# Schematic_v13.net
KiCad netlist of a schematic drawn in EAGLE
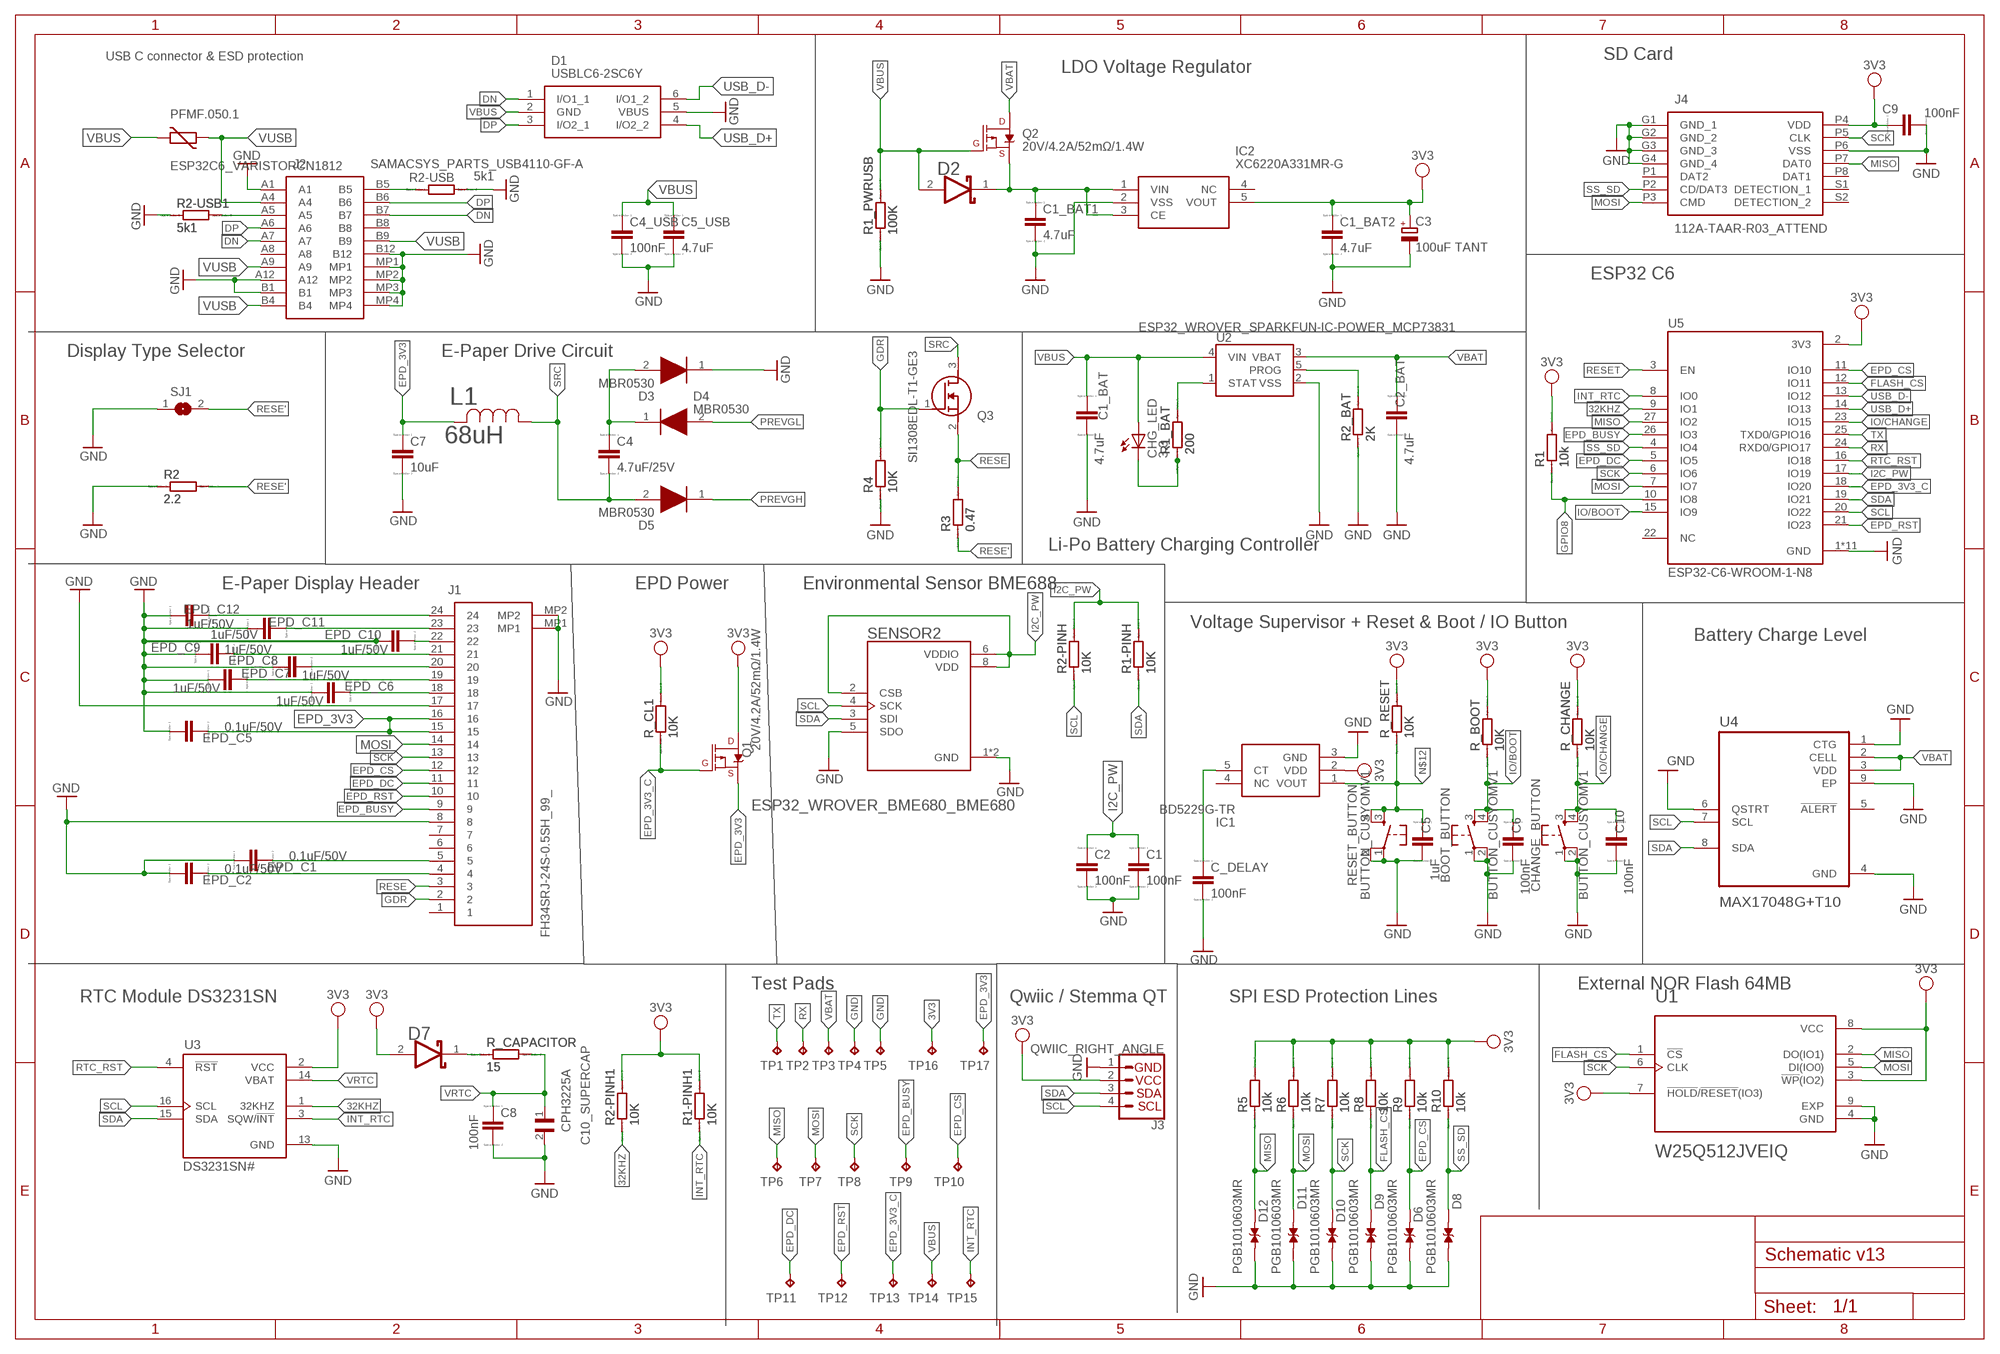
[diagram p0: schematic, sheet 1]

(export (version "E")
  (design (tool "Eeschema 10.0.6"))
  (components
    (comp (ref "BOOT_BUTTON")
      (value "BUTTON_CUSYOMV1")
      (footprint "eagle-import:MYBUTTON")
      (libsource (lib "eagle-import") (part "BUTTON_CUSYOMV1"))
    )
    (comp (ref "C1")
      (value "100nF")
      (footprint "eagle-import:ESP32_WROVER_EAGLE-LTSPICE_C0402")
      (libsource (lib "eagle-import") (part "ESP32_WROVER_EAGLE-LTSPICE_CC0402"))
    )
    (comp (ref "C1_BAT")
      (value "4.7uF")
      (footprint "eagle-import:ESP32_WROVER_EAGLE-LTSPICE_C0402")
      (libsource (lib "eagle-import") (part "ESP32_WROVER_EAGLE-LTSPICE_CC0402"))
    )
    (comp (ref "C1_BAT1")
      (value "4.7uF")
      (footprint "eagle-import:EAGLE-LTSPICE_C0402")
      (libsource (lib "eagle-import") (part "EAGLE-LTSPICE_CC0402"))
    )
    (comp (ref "C1_BAT2")
      (value "4.7uF")
      (footprint "eagle-import:EAGLE-LTSPICE_C0402")
      (libsource (lib "eagle-import") (part "EAGLE-LTSPICE_CC0402"))
    )
    (comp (ref "C2")
      (value "100nF")
      (footprint "eagle-import:ESP32_WROVER_EAGLE-LTSPICE_C0402")
      (libsource (lib "eagle-import") (part "ESP32_WROVER_EAGLE-LTSPICE_CC0402"))
    )
    (comp (ref "C2_BAT")
      (value "4.7uF")
      (footprint "eagle-import:ESP32_WROVER_EAGLE-LTSPICE_C0402")
      (libsource (lib "eagle-import") (part "ESP32_WROVER_EAGLE-LTSPICE_CC0402"))
    )
    (comp (ref "C3")
      (value "100uF TANT")
      (footprint "eagle-import:RCL_CT3528")
      (libsource (lib "eagle-import") (part "RCL_CPOL-EUCT3528"))
    )
    (comp (ref "C4")
      (value "4.7uF/25V")
      (footprint "eagle-import:ESP32_WROVER_EAGLE-LTSPICE_C0402")
      (libsource (lib "eagle-import") (part "ESP32_WROVER_EAGLE-LTSPICE_CC0402"))
    )
    (comp (ref "C4_USB")
      (value "100nF")
      (footprint "eagle-import:ESP32_WROVER_EAGLE-LTSPICE_C0402")
      (libsource (lib "eagle-import") (part "ESP32_WROVER_EAGLE-LTSPICE_CC0402"))
    )
    (comp (ref "C5")
      (value "1uF")
      (footprint "eagle-import:ESP32_WROVER_EAGLE-LTSPICE_C0402")
      (libsource (lib "eagle-import") (part "ESP32_WROVER_EAGLE-LTSPICE_CC0402"))
    )
    (comp (ref "C5_USB")
      (value "4.7uF")
      (footprint "eagle-import:ESP32_WROVER_EAGLE-LTSPICE_C0402")
      (libsource (lib "eagle-import") (part "ESP32_WROVER_EAGLE-LTSPICE_CC0402"))
    )
    (comp (ref "C6")
      (value "100nF")
      (footprint "eagle-import:ESP32_WROVER_EAGLE-LTSPICE_C0402")
      (libsource (lib "eagle-import") (part "ESP32_WROVER_EAGLE-LTSPICE_CC0402"))
    )
    (comp (ref "C7")
      (value "10uF")
      (footprint "eagle-import:ESP32_WROVER_EAGLE-LTSPICE_C0402")
      (libsource (lib "eagle-import") (part "ESP32_WROVER_EAGLE-LTSPICE_CC0402"))
    )
    (comp (ref "C8")
      (value "100nF")
      (footprint "eagle-import:ESP32_WROVER_EAGLE-LTSPICE_C0402")
      (libsource (lib "eagle-import") (part "ESP32_WROVER_EAGLE-LTSPICE_CC0402"))
    )
    (comp (ref "C9")
      (value "100nF")
      (footprint "eagle-import:ESP32_WROVER_EAGLE-LTSPICE_C0402")
      (libsource (lib "eagle-import") (part "ESP32_WROVER_EAGLE-LTSPICE_CC0402"))
    )
    (comp (ref "C10")
      (value "100nF")
      (footprint "eagle-import:ESP32_WROVER_EAGLE-LTSPICE_C0402")
      (libsource (lib "eagle-import") (part "ESP32_WROVER_EAGLE-LTSPICE_CC0402"))
    )
    (comp (ref "C10_SUPERCAP")
      (value "CPH3225A")
      (footprint "eagle-import:CAPCP3225X100N")
      (fields (field (name "MF") "Seiko Instruments"))
      (libsource (lib "eagle-import") (part "CPH3225A"))
    )
    (comp (ref "CHANGE_BUTTON")
      (value "BUTTON_CUSYOMV1")
      (footprint "eagle-import:MYBUTTON")
      (libsource (lib "eagle-import") (part "BUTTON_CUSYOMV1"))
    )
    (comp (ref "CHG_LED")
      (value "3.3")
      (footprint "eagle-import:ADAFRUIT_CHIP-LED0603")
      (libsource (lib "eagle-import") (part "ADAFRUIT_LEDCHIP-LED0603"))
    )
    (comp (ref "C_DELAY")
      (value "100nF")
      (footprint "eagle-import:ESP32_WROVER_EAGLE-LTSPICE_C0402")
      (libsource (lib "eagle-import") (part "ESP32_WROVER_EAGLE-LTSPICE_CC0402"))
    )
    (comp (ref "D1")
      (value "USBLC6-2SC6Y")
      (footprint "eagle-import:SOT95P280X145-6N")
      (fields (field (name "MF") "STMicroelectronics"))
      (libsource (lib "eagle-import") (part "USBLC6-2SC6Y"))
    )
    (comp (ref "D2")
      (value "ESP32_WROVER_AVX---SD0805S020S1R0_AVX_SD0805S020S1R0_0_0AVX_SD0805S020S1R0_0_0")
      (footprint "eagle-import:ESP32_WROVER_AVX---SD0805S020S1R0_AVX_SD0805S020S1R0_0")
      (fields
        (field (name "DIGIKEY_PART_NUMBER") "478-7800-1-ND")
        (field (name "MF") "AVX")
        (field (name "MOUSER_PART_NUMBER") "581-SD0805S020S1R0")
      )
      (libsource (lib "eagle-import") (part "ESP32_WROVER_AVX---SD0805S020S1R0_AVX_SD0805S020S1R0_0_0AVX_SD0805S020S1R0_0_0"))
    )
    (comp (ref "D3")
      (value "MBR0530")
      (footprint "eagle-import:SOD3716X135N")
      (fields (field (name "MF") "ON Semiconductor"))
      (libsource (lib "eagle-import") (part "MBR0530"))
    )
    (comp (ref "D4")
      (value "MBR0530")
      (footprint "eagle-import:SOD3716X135N")
      (fields (field (name "MF") "ON Semiconductor"))
      (libsource (lib "eagle-import") (part "MBR0530"))
    )
    (comp (ref "D5")
      (value "MBR0530")
      (footprint "eagle-import:SOD3716X135N")
      (fields (field (name "MF") "ON Semiconductor"))
      (libsource (lib "eagle-import") (part "MBR0530"))
    )
    (comp (ref "D6")
      (value "PGB1010603MR")
      (footprint "eagle-import:DIOC1608X36N")
      (fields (field (name "MF") "Littelfuse Inc."))
      (libsource (lib "eagle-import") (part "PGB1010603MR"))
    )
    (comp (ref "D7")
      (value "ESP32_WROVER_AVX---SD0805S020S1R0_AVX_SD0805S020S1R0_0_0AVX_SD0805S020S1R0_0_0")
      (footprint "eagle-import:ESP32_WROVER_AVX---SD0805S020S1R0_AVX_SD0805S020S1R0_0")
      (fields
        (field (name "DIGIKEY_PART_NUMBER") "478-7800-1-ND")
        (field (name "MF") "AVX")
        (field (name "MOUSER_PART_NUMBER") "581-SD0805S020S1R0")
      )
      (libsource (lib "eagle-import") (part "ESP32_WROVER_AVX---SD0805S020S1R0_AVX_SD0805S020S1R0_0_0AVX_SD0805S020S1R0_0_0"))
    )
    (comp (ref "D8")
      (value "PGB1010603MR")
      (footprint "eagle-import:DIOC1608X36N")
      (fields (field (name "MF") "Littelfuse Inc."))
      (libsource (lib "eagle-import") (part "PGB1010603MR"))
    )
    (comp (ref "D9")
      (value "PGB1010603MR")
      (footprint "eagle-import:DIOC1608X36N")
      (fields (field (name "MF") "Littelfuse Inc."))
      (libsource (lib "eagle-import") (part "PGB1010603MR"))
    )
    (comp (ref "D10")
      (value "PGB1010603MR")
      (footprint "eagle-import:DIOC1608X36N")
      (fields (field (name "MF") "Littelfuse Inc."))
      (libsource (lib "eagle-import") (part "PGB1010603MR"))
    )
    (comp (ref "D11")
      (value "PGB1010603MR")
      (footprint "eagle-import:DIOC1608X36N")
      (fields (field (name "MF") "Littelfuse Inc."))
      (libsource (lib "eagle-import") (part "PGB1010603MR"))
    )
    (comp (ref "D12")
      (value "PGB1010603MR")
      (footprint "eagle-import:DIOC1608X36N")
      (fields (field (name "MF") "Littelfuse Inc."))
      (libsource (lib "eagle-import") (part "PGB1010603MR"))
    )
    (comp (ref "EPD_C1")
      (value "0.1uF/50V")
      (footprint "eagle-import:ESP32_WROVER_EAGLE-LTSPICE_C0402")
      (libsource (lib "eagle-import") (part "ESP32_WROVER_EAGLE-LTSPICE_CC0402"))
    )
    (comp (ref "EPD_C2")
      (value "0.1uF/50V")
      (footprint "eagle-import:ESP32_WROVER_EAGLE-LTSPICE_C0402")
      (libsource (lib "eagle-import") (part "ESP32_WROVER_EAGLE-LTSPICE_CC0402"))
    )
    (comp (ref "EPD_C5")
      (value "0.1uF/50V")
      (footprint "eagle-import:ESP32_WROVER_EAGLE-LTSPICE_C0402")
      (libsource (lib "eagle-import") (part "ESP32_WROVER_EAGLE-LTSPICE_CC0402"))
    )
    (comp (ref "EPD_C6")
      (value "1uF/50V")
      (footprint "eagle-import:ESP32_WROVER_EAGLE-LTSPICE_C0402")
      (libsource (lib "eagle-import") (part "ESP32_WROVER_EAGLE-LTSPICE_CC0402"))
    )
    (comp (ref "EPD_C7")
      (value "1uF/50V")
      (footprint "eagle-import:ESP32_WROVER_EAGLE-LTSPICE_C0402")
      (libsource (lib "eagle-import") (part "ESP32_WROVER_EAGLE-LTSPICE_CC0402"))
    )
    (comp (ref "EPD_C8")
      (value "1uF/50V")
      (footprint "eagle-import:ESP32_WROVER_EAGLE-LTSPICE_C0402")
      (libsource (lib "eagle-import") (part "ESP32_WROVER_EAGLE-LTSPICE_CC0402"))
    )
    (comp (ref "EPD_C9")
      (value "1uF/50V")
      (footprint "eagle-import:ESP32_WROVER_EAGLE-LTSPICE_C0402")
      (libsource (lib "eagle-import") (part "ESP32_WROVER_EAGLE-LTSPICE_CC0402"))
    )
    (comp (ref "EPD_C10")
      (value "1uF/50V")
      (footprint "eagle-import:ESP32_WROVER_EAGLE-LTSPICE_C0402")
      (libsource (lib "eagle-import") (part "ESP32_WROVER_EAGLE-LTSPICE_CC0402"))
    )
    (comp (ref "EPD_C11")
      (value "1uF/50V")
      (footprint "eagle-import:ESP32_WROVER_EAGLE-LTSPICE_C0402")
      (libsource (lib "eagle-import") (part "ESP32_WROVER_EAGLE-LTSPICE_CC0402"))
    )
    (comp (ref "EPD_C12")
      (value "1uF/50V")
      (footprint "eagle-import:ESP32_WROVER_EAGLE-LTSPICE_C0402")
      (libsource (lib "eagle-import") (part "ESP32_WROVER_EAGLE-LTSPICE_CC0402"))
    )
    (comp (ref "IC1")
      (value "BD5229G-TR")
      (footprint "eagle-import:SOT95P280X125-5N")
      (fields (field (name "MOUSER_PART_NUMBER") "755-BD5229G-TR"))
      (libsource (lib "eagle-import") (part "BD5229G-TR"))
    )
    (comp (ref "IC2")
      (value "XC6220A331MR-G")
      (footprint "eagle-import:SOT95P280X120-5N")
      (fields (field (name "MOUSER_PART_NUMBER") "865-XC6220A331MR-G"))
      (libsource (lib "eagle-import") (part "XC6220A331MR-G"))
    )
    (comp (ref "J1")
      (value "FH34SRJ-24S-0.5SH_99_")
      (footprint "eagle-import:FH34SRJ24S05SH99")
      (fields
        (field (name "MANUFACTURER_PART_NUMBER") "FH34SRJ-24S-0.5SH(99)")
        (field (name "MOUSER_PART_NUMBER") "798-FH34SRJ24S05SH99")
      )
      (libsource (lib "eagle-import") (part "FH34SRJ-24S-0.5SH_99_"))
    )
    (comp (ref "J2")
      (value "SAMACSYS_PARTS_USB4110-GF-A")
      (footprint "eagle-import:SAMACSYS_PARTS_USB4110GFA")
      (fields
        (field (name "MANUFACTURER_PART_NUMBER") "USB4110-GF-A")
        (field (name "MOUSER_PART_NUMBER") "640-USB4110-GF-A")
      )
      (libsource (lib "eagle-import") (part "SAMACSYS_PARTS_USB4110-GF-A"))
    )
    (comp (ref "J3")
      (value "QWIIC_RIGHT_ANGLE")
      (footprint "eagle-import:JST04_1MM_RA")
      (libsource (lib "eagle-import") (part "QWIIC_CONNECTORJS-1MM"))
    )
    (comp (ref "J4")
      (value "112A-TAAR-R03_ATTEND")
      (footprint "eagle-import:112ATAARR03ATTEND")
      (fields (field (name "MANUFACTURER_PART_NUMBER") "112A-TAAR-R03 ATTEND"))
      (libsource (lib "eagle-import") (part "112A-TAAR-R03_ATTEND"))
    )
    (comp (ref "L1")
      (value "68uH")
      (footprint "eagle-import:IND_4828-WE-TPC_WRE")
      (fields
        (field (name "MANUFACTURER_PART_NUMBER") "744043680")
        (field (name "COPYRIGHT") "Copyright (C) 2024 Ultra Librarian. All rights reserved.")
      )
      (libsource (lib "eagle-import") (part "744043680IND_4828-WE-TPC_WRE"))
    )
    (comp (ref "PFMF.050.1")
      (value "ESP32C6_VARISTORCN1812")
      (footprint "eagle-import:ESP32C6_VARISTOR_CT_CN1812")
      (libsource (lib "eagle-import") (part "ESP32C6_VARISTORCN1812"))
    )
    (comp (ref "Q1")
      (value "20V/4.2A/52mΩ/1.4W")
      (footprint "eagle-import:ESP32_WROVER_SPARKFUN-DISCRETESEMI_SOT23-3")
      (libsource (lib "eagle-import") (part "ESP32_WROVER_SPARKFUN-DISCRETESEMI_MOSFET_PCH-DMG2305UX-7"))
    )
    (comp (ref "Q2")
      (value "20V/4.2A/52mΩ/1.4W")
      (footprint "eagle-import:ESP32_WROVER_SPARKFUN-DISCRETESEMI_SOT23-3")
      (libsource (lib "eagle-import") (part "ESP32_WROVER_SPARKFUN-DISCRETESEMI_MOSFET_PCH-DMG2305UX-7"))
    )
    (comp (ref "Q3")
      (value "SI1308EDL-T1-GE3")
      (footprint "eagle-import:SOT65P210X110-3N")
      (fields (field (name "MF") "Vishay Siliconix"))
      (libsource (lib "eagle-import") (part "SI1308EDL-T1-GE3"))
    )
    (comp (ref "R1")
      (value "10k")
      (footprint "eagle-import:ESP32_WROVER_EAGLE-LTSPICE_R0402")
      (libsource (lib "eagle-import") (part "ESP32_WROVER_EAGLE-LTSPICE_RR0402"))
    )
    (comp (ref "R1-PINH")
      (value "10K")
      (footprint "eagle-import:ESP32_WROVER_EAGLE-LTSPICE_R0402")
      (libsource (lib "eagle-import") (part "ESP32_WROVER_EAGLE-LTSPICE_RR0402"))
    )
    (comp (ref "R1-PINH1")
      (value "10K")
      (footprint "eagle-import:ESP32_WROVER_EAGLE-LTSPICE_R0402")
      (libsource (lib "eagle-import") (part "ESP32_WROVER_EAGLE-LTSPICE_RR0402"))
    )
    (comp (ref "R1_BAT")
      (value "200")
      (footprint "eagle-import:ESP32_WROVER_EAGLE-LTSPICE_R0402")
      (libsource (lib "eagle-import") (part "ESP32_WROVER_EAGLE-LTSPICE_RR0402"))
    )
    (comp (ref "R1_PWRUSB")
      (value "100K")
      (footprint "eagle-import:ESP32_WROVER_EAGLE-LTSPICE_R0402")
      (libsource (lib "eagle-import") (part "ESP32_WROVER_EAGLE-LTSPICE_RR0402"))
    )
    (comp (ref "R2")
      (value "2.2")
      (footprint "eagle-import:ESP32_WROVER_EAGLE-LTSPICE_R0402")
      (libsource (lib "eagle-import") (part "ESP32_WROVER_EAGLE-LTSPICE_RR0402"))
    )
    (comp (ref "R2-PINH")
      (value "10K")
      (footprint "eagle-import:ESP32_WROVER_EAGLE-LTSPICE_R0402")
      (libsource (lib "eagle-import") (part "ESP32_WROVER_EAGLE-LTSPICE_RR0402"))
    )
    (comp (ref "R2-PINH1")
      (value "10K")
      (footprint "eagle-import:ESP32_WROVER_EAGLE-LTSPICE_R0402")
      (libsource (lib "eagle-import") (part "ESP32_WROVER_EAGLE-LTSPICE_RR0402"))
    )
    (comp (ref "R2-USB")
      (value "5k1")
      (footprint "eagle-import:ESP32_WROVER_EAGLE-LTSPICE_R0402")
      (libsource (lib "eagle-import") (part "ESP32_WROVER_EAGLE-LTSPICE_RR0402"))
    )
    (comp (ref "R2-USB1")
      (value "5k1")
      (footprint "eagle-import:ESP32_WROVER_EAGLE-LTSPICE_R0402")
      (libsource (lib "eagle-import") (part "ESP32_WROVER_EAGLE-LTSPICE_RR0402"))
    )
    (comp (ref "R2_BAT")
      (value "2K")
      (footprint "eagle-import:ESP32_WROVER_EAGLE-LTSPICE_R0402")
      (libsource (lib "eagle-import") (part "ESP32_WROVER_EAGLE-LTSPICE_RR0402"))
    )
    (comp (ref "R3")
      (value "0.47")
      (footprint "eagle-import:ESP32_WROVER_EAGLE-LTSPICE_R0402")
      (libsource (lib "eagle-import") (part "ESP32_WROVER_EAGLE-LTSPICE_RR0402"))
    )
    (comp (ref "R4")
      (value "10K")
      (footprint "eagle-import:ESP32_WROVER_EAGLE-LTSPICE_R0402")
      (libsource (lib "eagle-import") (part "ESP32_WROVER_EAGLE-LTSPICE_RR0402"))
    )
    (comp (ref "R5")
      (value "10k")
      (footprint "eagle-import:ESP32_WROVER_EAGLE-LTSPICE_R0402")
      (libsource (lib "eagle-import") (part "ESP32_WROVER_EAGLE-LTSPICE_RR0402"))
    )
    (comp (ref "R6")
      (value "10k")
      (footprint "eagle-import:ESP32_WROVER_EAGLE-LTSPICE_R0402")
      (libsource (lib "eagle-import") (part "ESP32_WROVER_EAGLE-LTSPICE_RR0402"))
    )
    (comp (ref "R7")
      (value "10k")
      (footprint "eagle-import:ESP32_WROVER_EAGLE-LTSPICE_R0402")
      (libsource (lib "eagle-import") (part "ESP32_WROVER_EAGLE-LTSPICE_RR0402"))
    )
    (comp (ref "R8")
      (value "10k")
      (footprint "eagle-import:ESP32_WROVER_EAGLE-LTSPICE_R0402")
      (libsource (lib "eagle-import") (part "ESP32_WROVER_EAGLE-LTSPICE_RR0402"))
    )
    (comp (ref "R9")
      (value "10k")
      (footprint "eagle-import:ESP32_WROVER_EAGLE-LTSPICE_R0402")
      (libsource (lib "eagle-import") (part "ESP32_WROVER_EAGLE-LTSPICE_RR0402"))
    )
    (comp (ref "R10")
      (value "10k")
      (footprint "eagle-import:ESP32_WROVER_EAGLE-LTSPICE_R0402")
      (libsource (lib "eagle-import") (part "ESP32_WROVER_EAGLE-LTSPICE_RR0402"))
    )
    (comp (ref "RESET_BUTTON")
      (value "BUTTON_CUSYOMV1")
      (footprint "eagle-import:MYBUTTON")
      (libsource (lib "eagle-import") (part "BUTTON_CUSYOMV1"))
    )
    (comp (ref "R_BOOT")
      (value "10K")
      (footprint "eagle-import:ESP32_WROVER_EAGLE-LTSPICE_R0402")
      (libsource (lib "eagle-import") (part "ESP32_WROVER_EAGLE-LTSPICE_RR0402"))
    )
    (comp (ref "R_CAPACITOR")
      (value "15")
      (footprint "eagle-import:ESP32_WROVER_EAGLE-LTSPICE_R0402")
      (libsource (lib "eagle-import") (part "ESP32_WROVER_EAGLE-LTSPICE_RR0402"))
    )
    (comp (ref "R_CHANGE")
      (value "10K")
      (footprint "eagle-import:ESP32_WROVER_EAGLE-LTSPICE_R0402")
      (libsource (lib "eagle-import") (part "ESP32_WROVER_EAGLE-LTSPICE_RR0402"))
    )
    (comp (ref "R_CL1")
      (value "10K")
      (footprint "eagle-import:ESP32_WROVER_EAGLE-LTSPICE_R0402")
      (libsource (lib "eagle-import") (part "ESP32_WROVER_EAGLE-LTSPICE_RR0402"))
    )
    (comp (ref "R_RESET")
      (value "10K")
      (footprint "eagle-import:ESP32_WROVER_EAGLE-LTSPICE_R0402")
      (libsource (lib "eagle-import") (part "ESP32_WROVER_EAGLE-LTSPICE_RR0402"))
    )
    (comp (ref "SENSOR2")
      (value "ESP32_WROVER_BME680_BME680")
      (footprint "eagle-import:ESP32_WROVER_BME680_PSON80P300X300X100-8N")
      (fields (field (name "MF") "Bosch Sensortec") (field (name "MP") "BME680"))
      (libsource (lib "eagle-import") (part "ESP32_WROVER_BME680_BME680"))
    )
    (comp (ref "SJ1") (value "SJ") (footprint "eagle-import:SJ") (libsource (lib "eagle-import") (part "SJ")))
    (comp (ref "TP1")
      (value "TPTP20R")
      (footprint "eagle-import:TP20R")
      (libsource (lib "eagle-import") (part "TPTP20R"))
    )
    (comp (ref "TP2")
      (value "TPTP20R")
      (footprint "eagle-import:TP20R")
      (libsource (lib "eagle-import") (part "TPTP20R"))
    )
    (comp (ref "TP3")
      (value "TPTP20R")
      (footprint "eagle-import:TP20R")
      (libsource (lib "eagle-import") (part "TPTP20R"))
    )
    (comp (ref "TP4")
      (value "TPTP20R")
      (footprint "eagle-import:TP20R")
      (libsource (lib "eagle-import") (part "TPTP20R"))
    )
    (comp (ref "TP5")
      (value "TPTP20R")
      (footprint "eagle-import:TP20R")
      (libsource (lib "eagle-import") (part "TPTP20R"))
    )
    (comp (ref "TP6")
      (value "TPTP20R")
      (footprint "eagle-import:TP20R")
      (libsource (lib "eagle-import") (part "TPTP20R"))
    )
    (comp (ref "TP7")
      (value "TPTP20R")
      (footprint "eagle-import:TP20R")
      (libsource (lib "eagle-import") (part "TPTP20R"))
    )
    (comp (ref "TP8")
      (value "TPTP20R")
      (footprint "eagle-import:TP20R")
      (libsource (lib "eagle-import") (part "TPTP20R"))
    )
    (comp (ref "TP9")
      (value "TPTP20R")
      (footprint "eagle-import:TP20R")
      (libsource (lib "eagle-import") (part "TPTP20R"))
    )
    (comp (ref "TP10")
      (value "TPTP20R")
      (footprint "eagle-import:TP20R")
      (libsource (lib "eagle-import") (part "TPTP20R"))
    )
    (comp (ref "TP11")
      (value "TPTP20R")
      (footprint "eagle-import:TP20R")
      (libsource (lib "eagle-import") (part "TPTP20R"))
    )
    (comp (ref "TP12")
      (value "TPTP20R")
      (footprint "eagle-import:TP20R")
      (libsource (lib "eagle-import") (part "TPTP20R"))
    )
    (comp (ref "TP13")
      (value "TPTP20R")
      (footprint "eagle-import:TP20R")
      (libsource (lib "eagle-import") (part "TPTP20R"))
    )
    (comp (ref "TP14")
      (value "TPTP20R")
      (footprint "eagle-import:TP20R")
      (libsource (lib "eagle-import") (part "TPTP20R"))
    )
    (comp (ref "TP15")
      (value "TPTP20R")
      (footprint "eagle-import:TP20R")
      (libsource (lib "eagle-import") (part "TPTP20R"))
    )
    (comp (ref "TP16")
      (value "TPTP20R")
      (footprint "eagle-import:TP20R")
      (libsource (lib "eagle-import") (part "TPTP20R"))
    )
    (comp (ref "TP17")
      (value "TPTP20R")
      (footprint "eagle-import:TP20R")
      (libsource (lib "eagle-import") (part "TPTP20R"))
    )
    (comp (ref "U1")
      (value "W25Q512JVEIQ")
      (footprint "eagle-import:SON127P600X800X80-9N")
      (fields (field (name "MF") "Winbond Electronics"))
      (libsource (lib "eagle-import") (part "W25Q512JVEIQ"))
    )
    (comp (ref "U2")
      (value "ESP32_WROVER_SPARKFUN-IC-POWER_MCP73831")
      (footprint "eagle-import:ESP32_WROVER_SPARKFUN-IC-POWER_SOT23-5")
      (libsource (lib "eagle-import") (part "ESP32_WROVER_SPARKFUN-IC-POWER_MCP73831"))
    )
    (comp (ref "U3")
      (value "DS3231SN#")
      (footprint "eagle-import:SOIC127P1032X265-16N")
      (fields (field (name "MF") "Analog Devices"))
      (libsource (lib "eagle-import") (part "DS3231SN#"))
    )
    (comp (ref "U4")
      (value "MAX17048G+T10")
      (footprint "eagle-import:SON50P200X200X80-9N")
      (fields (field (name "MF") "Analog Devices"))
      (libsource (lib "eagle-import") (part "MAX17048G+T10"))
    )
    (comp (ref "U5")
      (value "ESP32-C6-WROOM-1-N8")
      (footprint "eagle-import:XCVR_ESP32-C6-WROOM-1-N8")
      (fields (field (name "MF") "Espressif Systems"))
      (libsource (lib "eagle-import") (part "ESP32-C6-WROOM-1-N8"))
    )
  )
  (nets
    (net (code "1") (name "3V3") (class "Default")
      (node (ref "C1_BAT2") (pin "1") (pinfunction "1_1") (pintype "passive"))
      (node (ref "C3") (pin "+") (pinfunction "+_+") (pintype "passive"))
      (node (ref "C9") (pin "1") (pinfunction "1_1") (pintype "passive"))
      (node (ref "D7") (pin "2") (pinfunction "ANODE_2") (pintype "bidirectional"))
      (node (ref "IC1") (pin "2") (pinfunction "VDD_2") (pintype "bidirectional"))
      (node (ref "IC2") (pin "5") (pinfunction "VOUT_5") (pintype "bidirectional"))
      (node (ref "J3") (pin "2") (pinfunction "2_2") (pintype "power_in"))
      (node (ref "J4") (pin "P4") (pinfunction "VDD_P4") (pintype "bidirectional"))
      (node (ref "Q1") (pin "3") (pinfunction "D_3") (pintype "bidirectional"))
      (node (ref "R1") (pin "2") (pinfunction "2_2") (pintype "passive"))
      (node (ref "R1-PINH1") (pin "2") (pinfunction "2_2") (pintype "passive"))
      (node (ref "R10") (pin "2") (pinfunction "2_2") (pintype "passive"))
      (node (ref "R2-PINH1") (pin "2") (pinfunction "2_2") (pintype "passive"))
      (node (ref "R5") (pin "2") (pinfunction "2_2") (pintype "passive"))
      (node (ref "R6") (pin "2") (pinfunction "2_2") (pintype "passive"))
      (node (ref "R7") (pin "2") (pinfunction "2_2") (pintype "passive"))
      (node (ref "R8") (pin "2") (pinfunction "2_2") (pintype "passive"))
      (node (ref "R9") (pin "2") (pinfunction "2_2") (pintype "passive"))
      (node (ref "R_BOOT") (pin "2") (pinfunction "2_2") (pintype "passive"))
      (node (ref "R_CHANGE") (pin "2") (pinfunction "2_2") (pintype "passive"))
      (node (ref "R_CL1") (pin "2") (pinfunction "2_2") (pintype "passive"))
      (node (ref "R_RESET") (pin "2") (pinfunction "2_2") (pintype "passive"))
      (node (ref "TP16") (pin "TP") (pinfunction "TP_TP") (pintype "input"))
      (node (ref "U1") (pin "3") (pinfunction "~{WP}(IO2)_3") (pintype "bidirectional"))
      (node (ref "U1") (pin "7") (pinfunction "~{HOLD}/~{RESET}(IO3)_7") (pintype "bidirectional"))
      (node (ref "U1") (pin "8") (pinfunction "VCC_8") (pintype "power_in"))
      (node (ref "U3") (pin "2") (pinfunction "VCC_2") (pintype "power_in"))
      (node (ref "U5") (pin "2") (pinfunction "3V3_2") (pintype "power_in"))
    )
    (net (code "2") (name "32KHZ") (class "Default")
      (node (ref "R2-PINH1") (pin "1") (pinfunction "1_1") (pintype "passive"))
      (node (ref "U3") (pin "1") (pinfunction "32KHZ_1") (pintype "output"))
      (node (ref "U5") (pin "9") (pinfunction "IO1_9") (pintype "bidirectional"))
    )
    (net (code "3") (name "DN") (class "Default")
      (node (ref "D1") (pin "1") (pinfunction "I/O1_1_1") (pintype "bidirectional"))
      (node (ref "J2") (pin "A7") (pinfunction "A7_A7") (pintype "bidirectional"))
      (node (ref "J2") (pin "B7") (pinfunction "B7_B7") (pintype "bidirectional"))
    )
    (net (code "4") (name "DP") (class "Default")
      (node (ref "D1") (pin "3") (pinfunction "I/O2_1_3") (pintype "bidirectional"))
      (node (ref "J2") (pin "A6") (pinfunction "A6_A6") (pintype "bidirectional"))
      (node (ref "J2") (pin "B6") (pinfunction "B6_B6") (pintype "bidirectional"))
    )
    (net (code "5") (name "EPD_3V3") (class "Default")
      (node (ref "C7") (pin "1") (pinfunction "1_1") (pintype "passive"))
      (node (ref "EPD_C5") (pin "2") (pinfunction "2_2") (pintype "passive"))
      (node (ref "J1") (pin "15") (pinfunction "15_15") (pintype "bidirectional"))
      (node (ref "J1") (pin "16") (pinfunction "16_16") (pintype "bidirectional"))
      (node (ref "L1") (pin "2") (pinfunction "2_2") (pintype "passive"))
      (node (ref "Q1") (pin "2") (pinfunction "S_2") (pintype "bidirectional"))
      (node (ref "TP17") (pin "TP") (pinfunction "TP_TP") (pintype "input"))
    )
    (net (code "6") (name "EPD_3V3_C") (class "Default")
      (node (ref "Q1") (pin "1") (pinfunction "G_1") (pintype "bidirectional"))
      (node (ref "R_CL1") (pin "1") (pinfunction "1_1") (pintype "passive"))
      (node (ref "TP13") (pin "TP") (pinfunction "TP_TP") (pintype "input"))
      (node (ref "U5") (pin "18") (pinfunction "IO20_18") (pintype "bidirectional"))
    )
    (net (code "7") (name "EPD_BUSY") (class "Default")
      (node (ref "J1") (pin "9") (pinfunction "9_9") (pintype "bidirectional"))
      (node (ref "TP9") (pin "TP") (pinfunction "TP_TP") (pintype "input"))
      (node (ref "U5") (pin "26") (pinfunction "IO3_26") (pintype "bidirectional"))
    )
    (net (code "8") (name "EPD_CS") (class "Default")
      (node (ref "D6") (pin "2") (pinfunction "2_2") (pintype "passive"))
      (node (ref "J1") (pin "12") (pinfunction "12_12") (pintype "bidirectional"))
      (node (ref "R9") (pin "1") (pinfunction "1_1") (pintype "passive"))
      (node (ref "TP10") (pin "TP") (pinfunction "TP_TP") (pintype "input"))
      (node (ref "U5") (pin "11") (pinfunction "IO10_11") (pintype "bidirectional"))
    )
    (net (code "9") (name "EPD_DC") (class "Default")
      (node (ref "J1") (pin "11") (pinfunction "11_11") (pintype "bidirectional"))
      (node (ref "TP11") (pin "TP") (pinfunction "TP_TP") (pintype "input"))
      (node (ref "U5") (pin "5") (pinfunction "IO5_5") (pintype "bidirectional"))
    )
    (net (code "10") (name "EPD_RST") (class "Default")
      (node (ref "J1") (pin "10") (pinfunction "10_10") (pintype "bidirectional"))
      (node (ref "TP12") (pin "TP") (pinfunction "TP_TP") (pintype "input"))
      (node (ref "U5") (pin "21") (pinfunction "IO23_21") (pintype "bidirectional"))
    )
    (net (code "11") (name "FLASH_CS") (class "Default")
      (node (ref "D9") (pin "2") (pinfunction "2_2") (pintype "passive"))
      (node (ref "R8") (pin "1") (pinfunction "1_1") (pintype "passive"))
      (node (ref "U1") (pin "1") (pinfunction "~{CS}_1") (pintype "input"))
      (node (ref "U5") (pin "12") (pinfunction "IO11_12") (pintype "bidirectional"))
    )
    (net (code "12") (name "GDR") (class "Default")
      (node (ref "J1") (pin "2") (pinfunction "2_2") (pintype "bidirectional"))
      (node (ref "Q3") (pin "1") (pinfunction "G_1") (pintype "bidirectional"))
      (node (ref "R4") (pin "2") (pinfunction "2_2") (pintype "passive"))
    )
    (net (code "13") (name "GND") (class "Default")
      (node (ref "BOOT_BUTTON") (pin "1") (pinfunction "1_1") (pintype "passive"))
      (node (ref "BOOT_BUTTON") (pin "2") (pinfunction "2_2") (pintype "passive"))
      (node (ref "C1") (pin "2") (pinfunction "2_2") (pintype "passive"))
      (node (ref "C10") (pin "2") (pinfunction "2_2") (pintype "passive"))
      (node (ref "C10_SUPERCAP") (pin "2") (pinfunction "2_2") (pintype "passive"))
      (node (ref "C1_BAT") (pin "2") (pinfunction "2_2") (pintype "passive"))
      (node (ref "C1_BAT1") (pin "2") (pinfunction "2_2") (pintype "passive"))
      (node (ref "C1_BAT2") (pin "2") (pinfunction "2_2") (pintype "passive"))
      (node (ref "C2") (pin "2") (pinfunction "2_2") (pintype "passive"))
      (node (ref "C2_BAT") (pin "2") (pinfunction "2_2") (pintype "passive"))
      (node (ref "C3") (pin "-") (pinfunction "-_-") (pintype "passive"))
      (node (ref "C4_USB") (pin "2") (pinfunction "2_2") (pintype "passive"))
      (node (ref "C5") (pin "2") (pinfunction "2_2") (pintype "passive"))
      (node (ref "C5_USB") (pin "2") (pinfunction "2_2") (pintype "passive"))
      (node (ref "C6") (pin "2") (pinfunction "2_2") (pintype "passive"))
      (node (ref "C7") (pin "2") (pinfunction "2_2") (pintype "passive"))
      (node (ref "C8") (pin "2") (pinfunction "2_2") (pintype "passive"))
      (node (ref "C9") (pin "2") (pinfunction "2_2") (pintype "passive"))
      (node (ref "CHANGE_BUTTON") (pin "1") (pinfunction "1_1") (pintype "passive"))
      (node (ref "CHANGE_BUTTON") (pin "2") (pinfunction "2_2") (pintype "passive"))
      (node (ref "C_DELAY") (pin "2") (pinfunction "2_2") (pintype "passive"))
      (node (ref "D1") (pin "5") (pinfunction "VBUS_5") (pintype "bidirectional"))
      (node (ref "D10") (pin "1") (pinfunction "1_1") (pintype "passive"))
      (node (ref "D11") (pin "1") (pinfunction "1_1") (pintype "passive"))
      (node (ref "D12") (pin "1") (pinfunction "1_1") (pintype "passive"))
      (node (ref "D3") (pin "1") (pinfunction "K_1") (pintype "bidirectional"))
      (node (ref "D6") (pin "1") (pinfunction "1_1") (pintype "passive"))
      (node (ref "D8") (pin "1") (pinfunction "1_1") (pintype "passive"))
      (node (ref "D9") (pin "1") (pinfunction "1_1") (pintype "passive"))
      (node (ref "EPD_C1") (pin "1") (pinfunction "1_1") (pintype "passive"))
      (node (ref "EPD_C10") (pin "1") (pinfunction "1_1") (pintype "passive"))
      (node (ref "EPD_C11") (pin "1") (pinfunction "1_1") (pintype "passive"))
      (node (ref "EPD_C12") (pin "1") (pinfunction "1_1") (pintype "passive"))
      (node (ref "EPD_C2") (pin "1") (pinfunction "1_1") (pintype "passive"))
      (node (ref "EPD_C5") (pin "1") (pinfunction "1_1") (pintype "passive"))
      (node (ref "EPD_C6") (pin "1") (pinfunction "1_1") (pintype "passive"))
      (node (ref "EPD_C7") (pin "1") (pinfunction "1_1") (pintype "passive"))
      (node (ref "EPD_C8") (pin "1") (pinfunction "1_1") (pintype "passive"))
      (node (ref "EPD_C9") (pin "1") (pinfunction "1_1") (pintype "passive"))
      (node (ref "IC1") (pin "3") (pinfunction "GND_3") (pintype "bidirectional"))
      (node (ref "IC2") (pin "2") (pinfunction "VSS_2") (pintype "bidirectional"))
      (node (ref "J1") (pin "17") (pinfunction "17_17") (pintype "bidirectional"))
      (node (ref "J1") (pin "8") (pinfunction "8_8") (pintype "bidirectional"))
      (node (ref "J1") (pin "MP1") (pinfunction "MP1_MP1") (pintype "bidirectional"))
      (node (ref "J1") (pin "MP2") (pinfunction "MP2_MP2") (pintype "bidirectional"))
      (node (ref "J2") (pin "A1") (pinfunction "A1_A1") (pintype "bidirectional"))
      (node (ref "J2") (pin "A12") (pinfunction "A12_A12") (pintype "bidirectional"))
      (node (ref "J2") (pin "B1") (pinfunction "B1_B1") (pintype "bidirectional"))
      (node (ref "J2") (pin "B12") (pinfunction "B12_B12") (pintype "bidirectional"))
      (node (ref "J2") (pin "MP1") (pinfunction "MP1_MP1") (pintype "bidirectional"))
      (node (ref "J2") (pin "MP2") (pinfunction "MP2_MP2") (pintype "bidirectional"))
      (node (ref "J2") (pin "MP3") (pinfunction "MP3_MP3") (pintype "bidirectional"))
      (node (ref "J2") (pin "MP4") (pinfunction "MP4_MP4") (pintype "bidirectional"))
      (node (ref "J3") (pin "1") (pinfunction "1_1") (pintype "power_in"))
      (node (ref "J4") (pin "G1") (pinfunction "GND_1_G1") (pintype "bidirectional"))
      (node (ref "J4") (pin "G2") (pinfunction "GND_2_G2") (pintype "bidirectional"))
      (node (ref "J4") (pin "G3") (pinfunction "GND_3_G3") (pintype "bidirectional"))
      (node (ref "J4") (pin "G4") (pinfunction "GND_4_G4") (pintype "bidirectional"))
      (node (ref "J4") (pin "P6") (pinfunction "VSS_P6") (pintype "bidirectional"))
      (node (ref "R1_PWRUSB") (pin "1") (pinfunction "1_1") (pintype "passive"))
      (node (ref "R2") (pin "1") (pinfunction "1_1") (pintype "passive"))
      (node (ref "R2-USB") (pin "2") (pinfunction "2_2") (pintype "passive"))
      (node (ref "R2-USB1") (pin "1") (pinfunction "1_1") (pintype "passive"))
      (node (ref "R2_BAT") (pin "1") (pinfunction "1_1") (pintype "passive"))
      (node (ref "R4") (pin "1") (pinfunction "1_1") (pintype "passive"))
      (node (ref "RESET_BUTTON") (pin "1") (pinfunction "1_1") (pintype "passive"))
      (node (ref "RESET_BUTTON") (pin "2") (pinfunction "2_2") (pintype "passive"))
      (node (ref "SENSOR2") (pin "1") (pinfunction "GND_1") (pintype "power_in"))
      (node (ref "SENSOR2") (pin "5") (pinfunction "SDO_5") (pintype "bidirectional"))
      (node (ref "SENSOR2") (pin "7") (pinfunction "GND_7") (pintype "power_in"))
      (node (ref "SJ1") (pin "1") (pinfunction "1_1") (pintype "passive"))
      (node (ref "TP4") (pin "TP") (pinfunction "TP_TP") (pintype "input"))
      (node (ref "TP5") (pin "TP") (pinfunction "TP_TP") (pintype "input"))
      (node (ref "U1") (pin "4") (pinfunction "GND_4") (pintype "power_in"))
      (node (ref "U1") (pin "9") (pinfunction "EXP_9") (pintype "passive"))
      (node (ref "U2") (pin "2") (pinfunction "VSS_2") (pintype "power_in"))
      (node (ref "U3") (pin "13") (pinfunction "GND_13") (pintype "power_in"))
      (node (ref "U4") (pin "1") (pinfunction "CTG_1") (pintype "power_in"))
      (node (ref "U4") (pin "4") (pinfunction "GND_4") (pintype "power_in"))
      (node (ref "U4") (pin "6") (pinfunction "QSTRT_6") (pintype "input"))
      (node (ref "U4") (pin "9") (pinfunction "EP_9") (pintype "power_in"))
      (node (ref "U5") (pin "1") (pinfunction "GND_1") (pintype "power_in"))
      (node (ref "U5") (pin "28") (pinfunction "GND_28") (pintype "power_in"))
      (node (ref "U5") (pin "29_1") (pinfunction "GND_29_1") (pintype "power_in"))
      (node (ref "U5") (pin "29_2") (pinfunction "GND_29_2") (pintype "power_in"))
      (node (ref "U5") (pin "29_3") (pinfunction "GND_29_3") (pintype "power_in"))
      (node (ref "U5") (pin "29_4") (pinfunction "GND_29_4") (pintype "power_in"))
      (node (ref "U5") (pin "29_5") (pinfunction "GND_29_5") (pintype "power_in"))
      (node (ref "U5") (pin "29_6") (pinfunction "GND_29_6") (pintype "power_in"))
      (node (ref "U5") (pin "29_7") (pinfunction "GND_29_7") (pintype "power_in"))
      (node (ref "U5") (pin "29_8") (pinfunction "GND_29_8") (pintype "power_in"))
      (node (ref "U5") (pin "29_9") (pinfunction "GND_29_9") (pintype "power_in"))
    )
    (net (code "14") (name "GPIO8") (class "Default")
      (node (ref "R1") (pin "1") (pinfunction "1_1") (pintype "passive"))
      (node (ref "U5") (pin "10") (pinfunction "IO8_10") (pintype "bidirectional"))
    )
    (net (code "15") (name "I2C_PW") (class "Default")
      (node (ref "C1") (pin "1") (pinfunction "1_1") (pintype "passive"))
      (node (ref "C2") (pin "1") (pinfunction "1_1") (pintype "passive"))
      (node (ref "R1-PINH") (pin "2") (pinfunction "2_2") (pintype "passive"))
      (node (ref "R2-PINH") (pin "2") (pinfunction "2_2") (pintype "passive"))
      (node (ref "SENSOR2") (pin "2") (pinfunction "CSB_2") (pintype "input"))
      (node (ref "SENSOR2") (pin "6") (pinfunction "VDDIO_6") (pintype "power_in"))
      (node (ref "SENSOR2") (pin "8") (pinfunction "VDD_8") (pintype "power_in"))
      (node (ref "U5") (pin "17") (pinfunction "IO19_17") (pintype "bidirectional"))
    )
    (net (code "16") (name "INT_RTC") (class "Default")
      (node (ref "R1-PINH1") (pin "1") (pinfunction "1_1") (pintype "passive"))
      (node (ref "TP15") (pin "TP") (pinfunction "TP_TP") (pintype "input"))
      (node (ref "U3") (pin "3") (pinfunction "SQW/~{INT}_3") (pintype "output"))
      (node (ref "U5") (pin "8") (pinfunction "IO0_8") (pintype "bidirectional"))
    )
    (net (code "17") (name "IO{slash}BOOT") (class "Default")
      (node (ref "BOOT_BUTTON") (pin "3") (pinfunction "3_3") (pintype "passive"))
      (node (ref "BOOT_BUTTON") (pin "4") (pinfunction "4_4") (pintype "passive"))
      (node (ref "C6") (pin "1") (pinfunction "1_1") (pintype "passive"))
      (node (ref "R_BOOT") (pin "1") (pinfunction "1_1") (pintype "passive"))
      (node (ref "U5") (pin "15") (pinfunction "IO9_15") (pintype "bidirectional"))
    )
    (net (code "18") (name "IO{slash}CHANGE") (class "Default")
      (node (ref "C10") (pin "1") (pinfunction "1_1") (pintype "passive"))
      (node (ref "CHANGE_BUTTON") (pin "3") (pinfunction "3_3") (pintype "passive"))
      (node (ref "CHANGE_BUTTON") (pin "4") (pinfunction "4_4") (pintype "passive"))
      (node (ref "R_CHANGE") (pin "1") (pinfunction "1_1") (pintype "passive"))
      (node (ref "U5") (pin "23") (pinfunction "IO15_23") (pintype "bidirectional"))
    )
    (net (code "19") (name "MISO") (class "Default")
      (node (ref "D12") (pin "2") (pinfunction "2_2") (pintype "passive"))
      (node (ref "J4") (pin "P7") (pinfunction "DAT0_P7") (pintype "bidirectional"))
      (node (ref "R5") (pin "1") (pinfunction "1_1") (pintype "passive"))
      (node (ref "TP6") (pin "TP") (pinfunction "TP_TP") (pintype "input"))
      (node (ref "U1") (pin "2") (pinfunction "DO(IO1)_2") (pintype "bidirectional"))
      (node (ref "U5") (pin "27") (pinfunction "IO2_27") (pintype "bidirectional"))
    )
    (net (code "20") (name "MOSI") (class "Default")
      (node (ref "D11") (pin "2") (pinfunction "2_2") (pintype "passive"))
      (node (ref "J1") (pin "14") (pinfunction "14_14") (pintype "bidirectional"))
      (node (ref "J4") (pin "P3") (pinfunction "CMD_P3") (pintype "bidirectional"))
      (node (ref "R6") (pin "1") (pinfunction "1_1") (pintype "passive"))
      (node (ref "TP7") (pin "TP") (pinfunction "TP_TP") (pintype "input"))
      (node (ref "U1") (pin "5") (pinfunction "DI(IO0)_5") (pintype "bidirectional"))
      (node (ref "U5") (pin "7") (pinfunction "IO7_7") (pintype "bidirectional"))
    )
    (net (code "21") (name "N$12") (class "Default")
      (node (ref "C5") (pin "1") (pinfunction "1_1") (pintype "passive"))
      (node (ref "IC1") (pin "1") (pinfunction "VOUT_1") (pintype "bidirectional"))
      (node (ref "RESET_BUTTON") (pin "3") (pinfunction "3_3") (pintype "passive"))
      (node (ref "RESET_BUTTON") (pin "4") (pinfunction "4_4") (pintype "passive"))
      (node (ref "R_RESET") (pin "1") (pinfunction "1_1") (pintype "passive"))
    )
    (net (code "22") (name "Net-(CHG_LED-PadC)") (class "Default")
      (node (ref "CHG_LED") (pin "C") (pinfunction "C_C") (pintype "passive"))
      (node (ref "R1_BAT") (pin "1") (pinfunction "1_1") (pintype "passive"))
    )
    (net (code "23") (name "Net-(D2-CATHODE)") (class "Default")
      (node (ref "C1_BAT1") (pin "1") (pinfunction "1_1") (pintype "passive"))
      (node (ref "D2") (pin "1") (pinfunction "CATHODE_1") (pintype "bidirectional"))
      (node (ref "IC2") (pin "1") (pinfunction "VIN_1") (pintype "bidirectional"))
      (node (ref "IC2") (pin "3") (pinfunction "CE_3") (pintype "bidirectional"))
      (node (ref "Q2") (pin "2") (pinfunction "S_2") (pintype "bidirectional"))
    )
    (net (code "24") (name "Net-(D3-A)") (class "Default")
      (node (ref "C4") (pin "1") (pinfunction "1_1") (pintype "passive"))
      (node (ref "D3") (pin "2") (pinfunction "A_2") (pintype "bidirectional"))
      (node (ref "D4") (pin "1") (pinfunction "K_1") (pintype "bidirectional"))
    )
    (net (code "25") (name "Net-(D7-CATHODE)") (class "Default")
      (node (ref "D7") (pin "1") (pinfunction "CATHODE_1") (pintype "bidirectional"))
      (node (ref "R_CAPACITOR") (pin "1") (pinfunction "1_1") (pintype "passive"))
    )
    (net (code "26") (name "Net-(EPD_C1-Pad2)") (class "Default")
      (node (ref "EPD_C1") (pin "2") (pinfunction "2_2") (pintype "passive"))
      (node (ref "J1") (pin "5") (pinfunction "5_5") (pintype "bidirectional"))
    )
    (net (code "27") (name "Net-(EPD_C2-Pad2)") (class "Default")
      (node (ref "EPD_C2") (pin "2") (pinfunction "2_2") (pintype "passive"))
      (node (ref "J1") (pin "4") (pinfunction "4_4") (pintype "bidirectional"))
    )
    (net (code "28") (name "Net-(EPD_C6-Pad2)") (class "Default")
      (node (ref "EPD_C6") (pin "2") (pinfunction "2_2") (pintype "passive"))
      (node (ref "J1") (pin "18") (pinfunction "18_18") (pintype "bidirectional"))
    )
    (net (code "29") (name "Net-(EPD_C7-Pad2)") (class "Default")
      (node (ref "EPD_C7") (pin "2") (pinfunction "2_2") (pintype "passive"))
      (node (ref "J1") (pin "19") (pinfunction "19_19") (pintype "bidirectional"))
    )
    (net (code "30") (name "Net-(EPD_C8-Pad2)") (class "Default")
      (node (ref "EPD_C8") (pin "2") (pinfunction "2_2") (pintype "passive"))
      (node (ref "J1") (pin "20") (pinfunction "20_20") (pintype "bidirectional"))
    )
    (net (code "31") (name "Net-(EPD_C9-Pad2)") (class "Default")
      (node (ref "EPD_C9") (pin "2") (pinfunction "2_2") (pintype "passive"))
      (node (ref "J1") (pin "21") (pinfunction "21_21") (pintype "bidirectional"))
    )
    (net (code "32") (name "Net-(EPD_C10-Pad2)") (class "Default")
      (node (ref "EPD_C10") (pin "2") (pinfunction "2_2") (pintype "passive"))
      (node (ref "J1") (pin "22") (pinfunction "22_22") (pintype "bidirectional"))
    )
    (net (code "33") (name "Net-(EPD_C11-Pad2)") (class "Default")
      (node (ref "EPD_C11") (pin "2") (pinfunction "2_2") (pintype "passive"))
      (node (ref "J1") (pin "23") (pinfunction "23_23") (pintype "bidirectional"))
    )
    (net (code "34") (name "Net-(EPD_C12-Pad2)") (class "Default")
      (node (ref "EPD_C12") (pin "2") (pinfunction "2_2") (pintype "passive"))
      (node (ref "J1") (pin "24") (pinfunction "24_24") (pintype "bidirectional"))
    )
    (net (code "35") (name "Net-(IC1-CT)") (class "Default")
      (node (ref "C_DELAY") (pin "1") (pinfunction "1_1") (pintype "passive"))
      (node (ref "IC1") (pin "5") (pinfunction "CT_5") (pintype "bidirectional"))
    )
    (net (code "36") (name "Net-(J2-PadA5)") (class "Default")
      (node (ref "J2") (pin "A5") (pinfunction "A5_A5") (pintype "bidirectional"))
      (node (ref "R2-USB1") (pin "2") (pinfunction "2_2") (pintype "passive"))
    )
    (net (code "37") (name "Net-(J2-PadB5)") (class "Default")
      (node (ref "J2") (pin "B5") (pinfunction "B5_B5") (pintype "bidirectional"))
      (node (ref "R2-USB") (pin "1") (pinfunction "1_1") (pintype "passive"))
    )
    (net (code "38") (name "Net-(U2-PROG)") (class "Default")
      (node (ref "R2_BAT") (pin "2") (pinfunction "2_2") (pintype "passive"))
      (node (ref "U2") (pin "5") (pinfunction "PROG_5") (pintype "input"))
    )
    (net (code "39") (name "Net-(U2-STAT)") (class "Default")
      (node (ref "R1_BAT") (pin "2") (pinfunction "2_2") (pintype "passive"))
      (node (ref "U2") (pin "1") (pinfunction "STAT_1") (pintype "output"))
    )
    (net (code "40") (name "PREVGH") (class "Default")
      (node (ref "D5") (pin "1") (pinfunction "K_1") (pintype "bidirectional"))
    )
    (net (code "41") (name "PREVGL") (class "Default")
      (node (ref "D4") (pin "2") (pinfunction "A_2") (pintype "bidirectional"))
    )
    (net (code "42") (name "RESE") (class "Default")
      (node (ref "J1") (pin "3") (pinfunction "3_3") (pintype "bidirectional"))
      (node (ref "Q3") (pin "2") (pinfunction "S_2") (pintype "bidirectional"))
      (node (ref "R3") (pin "2") (pinfunction "2_2") (pintype "passive"))
    )
    (net (code "43") (name "RESE'") (class "Default")
      (node (ref "R2") (pin "2") (pinfunction "2_2") (pintype "passive"))
      (node (ref "R3") (pin "1") (pinfunction "1_1") (pintype "passive"))
      (node (ref "SJ1") (pin "2") (pinfunction "2_2") (pintype "passive"))
    )
    (net (code "44") (name "RESET") (class "Default")
      (node (ref "U5") (pin "3") (pinfunction "EN_3") (pintype "input"))
    )
    (net (code "45") (name "RTC_RST") (class "Default")
      (node (ref "U3") (pin "4") (pinfunction "~{RST}_4") (pintype "input"))
      (node (ref "U5") (pin "16") (pinfunction "IO18_16") (pintype "bidirectional"))
    )
    (net (code "46") (name "RX") (class "Default")
      (node (ref "TP2") (pin "TP") (pinfunction "TP_TP") (pintype "input"))
      (node (ref "U5") (pin "24") (pinfunction "RXD0/GPIO17_24") (pintype "bidirectional"))
    )
    (net (code "47") (name "SCK") (class "Default")
      (node (ref "D10") (pin "2") (pinfunction "2_2") (pintype "passive"))
      (node (ref "J1") (pin "13") (pinfunction "13_13") (pintype "bidirectional"))
      (node (ref "J4") (pin "P5") (pinfunction "CLK_P5") (pintype "bidirectional"))
      (node (ref "R7") (pin "1") (pinfunction "1_1") (pintype "passive"))
      (node (ref "TP8") (pin "TP") (pinfunction "TP_TP") (pintype "input"))
      (node (ref "U1") (pin "6") (pinfunction "CLK_6") (pintype "input"))
      (node (ref "U5") (pin "6") (pinfunction "IO6_6") (pintype "bidirectional"))
    )
    (net (code "48") (name "SCL") (class "Default")
      (node (ref "J3") (pin "4") (pinfunction "4_4") (pintype "passive"))
      (node (ref "R2-PINH") (pin "1") (pinfunction "1_1") (pintype "passive"))
      (node (ref "SENSOR2") (pin "4") (pinfunction "SCK_4") (pintype "input"))
      (node (ref "U3") (pin "16") (pinfunction "SCL_16") (pintype "input"))
      (node (ref "U4") (pin "7") (pinfunction "SCL_7") (pintype "input"))
      (node (ref "U5") (pin "20") (pinfunction "IO22_20") (pintype "bidirectional"))
    )
    (net (code "49") (name "SDA") (class "Default")
      (node (ref "J3") (pin "3") (pinfunction "3_3") (pintype "passive"))
      (node (ref "R1-PINH") (pin "1") (pinfunction "1_1") (pintype "passive"))
      (node (ref "SENSOR2") (pin "3") (pinfunction "SDI_3") (pintype "bidirectional"))
      (node (ref "U3") (pin "15") (pinfunction "SDA_15") (pintype "bidirectional"))
      (node (ref "U4") (pin "8") (pinfunction "SDA_8") (pintype "bidirectional"))
      (node (ref "U5") (pin "19") (pinfunction "IO21_19") (pintype "bidirectional"))
    )
    (net (code "50") (name "SRC") (class "Default")
      (node (ref "C4") (pin "2") (pinfunction "2_2") (pintype "passive"))
      (node (ref "D5") (pin "2") (pinfunction "A_2") (pintype "bidirectional"))
      (node (ref "L1") (pin "1") (pinfunction "1_1") (pintype "passive"))
      (node (ref "Q3") (pin "3") (pinfunction "D_3") (pintype "bidirectional"))
    )
    (net (code "51") (name "SS_SD") (class "Default")
      (node (ref "D8") (pin "2") (pinfunction "2_2") (pintype "passive"))
      (node (ref "J4") (pin "P2") (pinfunction "CD/DAT3_P2") (pintype "bidirectional"))
      (node (ref "R10") (pin "1") (pinfunction "1_1") (pintype "passive"))
      (node (ref "U5") (pin "4") (pinfunction "IO4_4") (pintype "bidirectional"))
    )
    (net (code "52") (name "TX") (class "Default")
      (node (ref "TP1") (pin "TP") (pinfunction "TP_TP") (pintype "input"))
      (node (ref "U5") (pin "25") (pinfunction "TXD0/GPIO16_25") (pintype "bidirectional"))
    )
    (net (code "53") (name "USB_D+") (class "Default")
      (node (ref "D1") (pin "4") (pinfunction "I/O2_2_4") (pintype "bidirectional"))
      (node (ref "U5") (pin "14") (pinfunction "IO13_14") (pintype "bidirectional"))
    )
    (net (code "54") (name "USB_D-") (class "Default")
      (node (ref "D1") (pin "6") (pinfunction "I/O1_2_6") (pintype "bidirectional"))
      (node (ref "U5") (pin "13") (pinfunction "IO12_13") (pintype "bidirectional"))
    )
    (net (code "55") (name "VBAT") (class "Default")
      (node (ref "C2_BAT") (pin "1") (pinfunction "1_1") (pintype "passive"))
      (node (ref "Q2") (pin "3") (pinfunction "D_3") (pintype "bidirectional"))
      (node (ref "TP3") (pin "TP") (pinfunction "TP_TP") (pintype "input"))
      (node (ref "U2") (pin "3") (pinfunction "VBAT_3") (pintype "power_in"))
      (node (ref "U4") (pin "2") (pinfunction "CELL_2") (pintype "power_in"))
      (node (ref "U4") (pin "3") (pinfunction "VDD_3") (pintype "power_in"))
    )
    (net (code "56") (name "VBUS") (class "Default")
      (node (ref "C1_BAT") (pin "1") (pinfunction "1_1") (pintype "passive"))
      (node (ref "C4_USB") (pin "1") (pinfunction "1_1") (pintype "passive"))
      (node (ref "C5_USB") (pin "1") (pinfunction "1_1") (pintype "passive"))
      (node (ref "CHG_LED") (pin "A") (pinfunction "A_A") (pintype "passive"))
      (node (ref "D1") (pin "2") (pinfunction "GND_2") (pintype "bidirectional"))
      (node (ref "D2") (pin "2") (pinfunction "ANODE_2") (pintype "bidirectional"))
      (node (ref "PFMF.050.1") (pin "2") (pinfunction "2_2") (pintype "passive"))
      (node (ref "Q2") (pin "1") (pinfunction "G_1") (pintype "bidirectional"))
      (node (ref "R1_PWRUSB") (pin "2") (pinfunction "2_2") (pintype "passive"))
      (node (ref "TP14") (pin "TP") (pinfunction "TP_TP") (pintype "input"))
      (node (ref "U2") (pin "4") (pinfunction "VIN_4") (pintype "power_in"))
    )
    (net (code "57") (name "VRTC") (class "Default")
      (node (ref "C10_SUPERCAP") (pin "1") (pinfunction "1_1") (pintype "passive"))
      (node (ref "C8") (pin "1") (pinfunction "1_1") (pintype "passive"))
      (node (ref "R_CAPACITOR") (pin "2") (pinfunction "2_2") (pintype "passive"))
      (node (ref "U3") (pin "14") (pinfunction "VBAT_14") (pintype "power_in"))
    )
    (net (code "58") (name "VUSB") (class "Default")
      (node (ref "J2") (pin "A4") (pinfunction "A4_A4") (pintype "bidirectional"))
      (node (ref "J2") (pin "A9") (pinfunction "A9_A9") (pintype "bidirectional"))
      (node (ref "J2") (pin "B4") (pinfunction "B4_B4") (pintype "bidirectional"))
      (node (ref "J2") (pin "B9") (pinfunction "B9_B9") (pintype "bidirectional"))
      (node (ref "PFMF.050.1") (pin "1") (pinfunction "1_1") (pintype "passive"))
    )
    (net (code "59") (name "unconnected-(IC1-NC-Pad4)") (class "Default")
      (node (ref "IC1") (pin "4") (pinfunction "NC_4") (pintype "no_connect"))
    )
    (net (code "60") (name "unconnected-(IC2-NC-Pad4)") (class "Default")
      (node (ref "IC2") (pin "4") (pinfunction "NC_4") (pintype "no_connect"))
    )
    (net (code "61") (name "unconnected-(J1-Pad1)") (class "Default")
      (node (ref "J1") (pin "1") (pinfunction "1_1") (pintype "bidirectional"))
    )
    (net (code "62") (name "unconnected-(J1-Pad6)") (class "Default")
      (node (ref "J1") (pin "6") (pinfunction "6_6") (pintype "bidirectional"))
    )
    (net (code "63") (name "unconnected-(J1-Pad7)") (class "Default")
      (node (ref "J1") (pin "7") (pinfunction "7_7") (pintype "bidirectional"))
    )
    (net (code "64") (name "unconnected-(J2-PadA8)") (class "Default")
      (node (ref "J2") (pin "A8") (pinfunction "A8_A8") (pintype "bidirectional"))
    )
    (net (code "65") (name "unconnected-(J2-PadB8)") (class "Default")
      (node (ref "J2") (pin "B8") (pinfunction "B8_B8") (pintype "bidirectional"))
    )
    (net (code "66") (name "unconnected-(J4-DAT1-PadP8)") (class "Default")
      (node (ref "J4") (pin "P8") (pinfunction "DAT1_P8") (pintype "bidirectional"))
    )
    (net (code "67") (name "unconnected-(J4-DAT2-PadP1)") (class "Default")
      (node (ref "J4") (pin "P1") (pinfunction "DAT2_P1") (pintype "bidirectional"))
    )
    (net (code "68") (name "unconnected-(J4-DETECTION_1-PadS1)") (class "Default")
      (node (ref "J4") (pin "S1") (pinfunction "DETECTION_1_S1") (pintype "bidirectional"))
    )
    (net (code "69") (name "unconnected-(J4-DETECTION_2-PadS2)") (class "Default")
      (node (ref "J4") (pin "S2") (pinfunction "DETECTION_2_S2") (pintype "bidirectional"))
    )
    (net (code "70") (name "unconnected-(U4-~{ALERT}-Pad5)") (class "Default")
      (node (ref "U4") (pin "5") (pinfunction "~{ALERT}_5") (pintype "output"))
    )
    (net (code "71") (name "unconnected-(U5-NC-Pad22)") (class "Default")
      (node (ref "U5") (pin "22") (pinfunction "NC_22") (pintype "no_connect"))
    )
  )
)
